# Constant_Current_Sink.net
KiCad netlist of a schematic drawn in Altium Designer
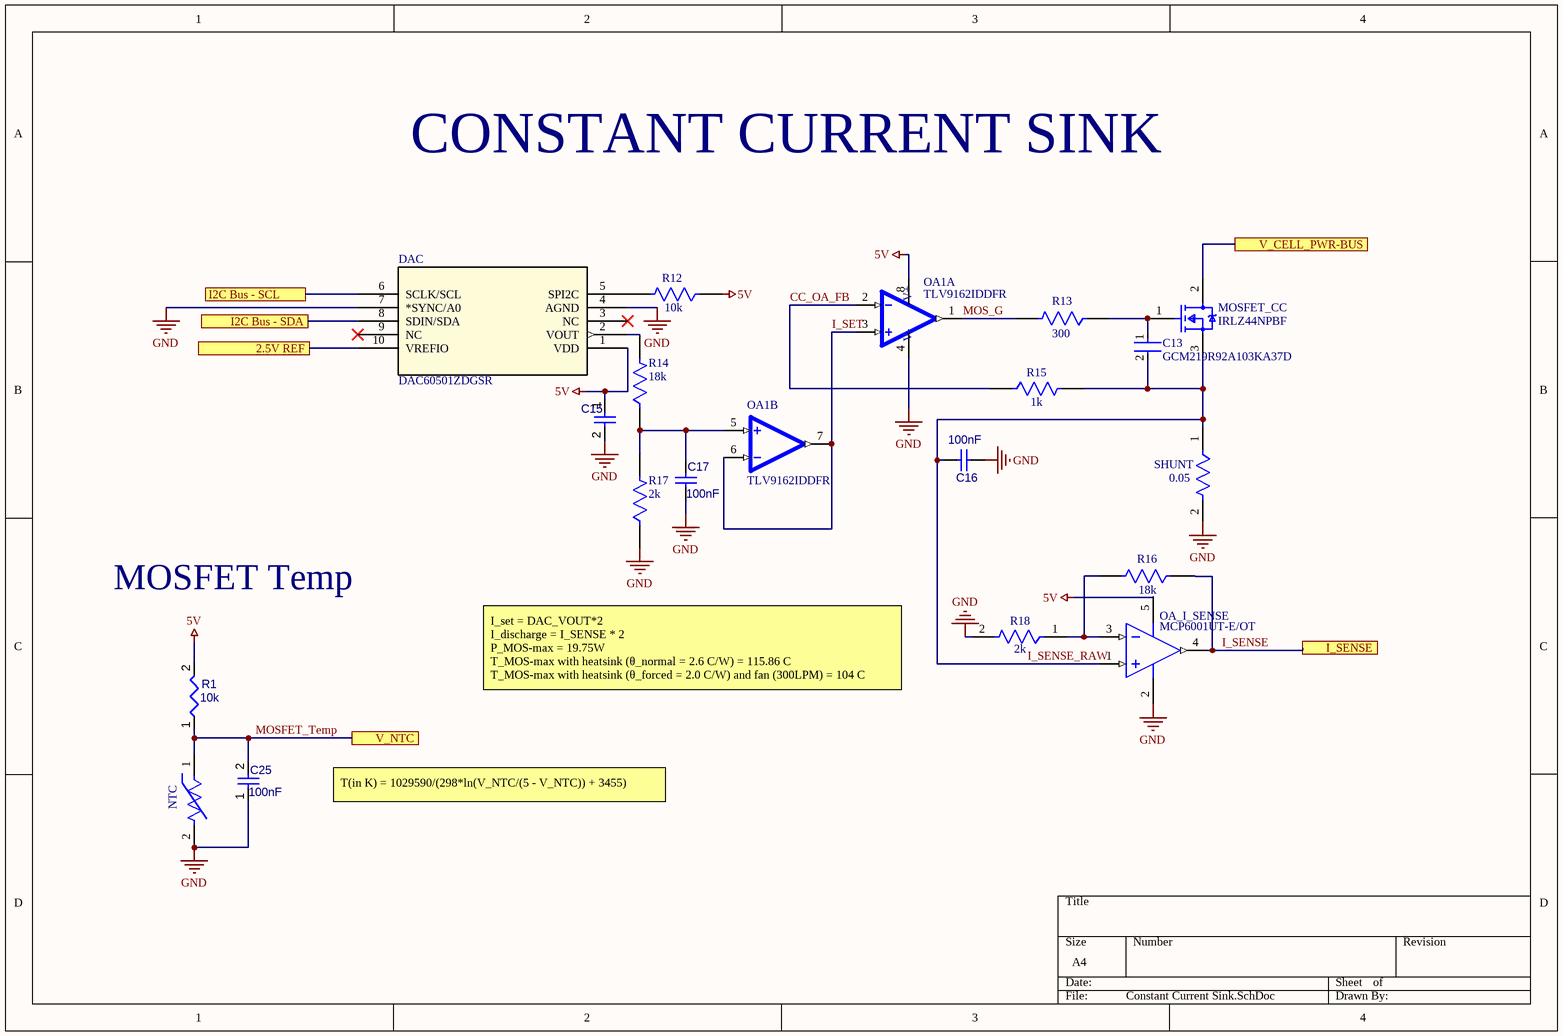
[diagram p0: Constant Current Sink.SchDoc]

(export (version "E")
  (design (tool "Eeschema 10.0.6"))
  (components
    (comp (ref "C13")
      (value "GCM219R92A103KA37D")
      (footprint "FP-GCM219-0_15-IPC_C")
      (description "Ceramic Capacitor for Automotive 10nF  ±10% 100VDC X8R 0805 Paper T/R")
      (libsource (lib "Altium Content Vault") (part "11868f565c42a9108669ba33697ecf6"))
    )
    (comp (ref "C15")
      (value "100nF")
      (footprint "CAPC2013X95X50LL10T25")
      (description "Capacitor 100 nF +/-10% 50 V 0805")
      (fields (field (name "TOLERANCE") "10%"))
      (libsource (lib "gugan Sivakumar") (part "CAP-NP-2"))
    )
    (comp (ref "C16")
      (value "100nF")
      (footprint "CAPC2013X95X50LL10T25")
      (description "Capacitor 100 nF +/-10% 50 V 0805")
      (fields (field (name "TOLERANCE") "10%"))
      (libsource (lib "") (part "CAP-NP-2_1"))
    )
    (comp (ref "C17")
      (value "100nF")
      (footprint "CAPC2013X95X50LL10T25")
      (description "Capacitor 100 nF +/-10% 50 V 0805")
      (fields (field (name "TOLERANCE") "10%"))
      (libsource (lib "") (part "CAP-NP-2_1"))
    )
    (comp (ref "C25")
      (value "100nF")
      (footprint "CAPC2013X95X50LL10T25")
      (description "Capacitor 100 nF +/-10% 50 V 0805")
      (fields (field (name "TOLERANCE") "10%"))
      (libsource (lib "gugan Sivakumar") (part "CAP-NP-2"))
    )
    (comp (ref "DAC")
      (value "DAC60501ZDGSR")
      (footprint "DGS10_TEX")
      (fields (field (name "COPYRIGHT") "Copyright (C) 2025 Ultra Librarian. All rights reserved."))
      (libsource (lib "DAC60501ZDGSR") (part "DAC60501ZDGSR"))
    )
    (comp (ref "MOSFET_CC")
      (value "IRLZ44NPBF")
      (footprint "FP-PG-TO220-3-MFG")
      (description "MOSFET N-CH 55V 47A TO220AB")
      (libsource (lib "Altium Content Vault") (part "b09f7f152735e370c1ea22a33fa83d6"))
    )
    (comp (ref "NTC")
      (value "NXRT15XH103FA1B030")
      (footprint "FP-NXR_151B030-MFG")
      (description "Thermistor NTC 10kΩ ±1% 2-Pin Radial Bulk")
      (fields (field (name "TOLERANCE") "1%"))
      (libsource (lib "Altium Content Vault") (part "3b148a6ebabc5fb4d708a66c052d352"))
    )
    (comp (ref "OA1")
      (value "TLV9162IDDFR")
      (footprint "SOT65P280X110-8N")
      (description "Dual, 16V, 11MHz, rail-to-rail input and output low-offset-voltage low-noise operational amplifier")
      (fields (field (name "MF") "Texas Instruments"))
      (libsource (lib "gugan Sivakumar") (part "TLV9162IDDFR"))
    )
    (comp (ref "OA_I_SENSE")
      (value "MCP6001UT-E/OT")
      (footprint "SOT-23-OT5_L")
      (description "None")
      (libsource (lib "Altium Content Vault") (part "AMP-OPA-MCP6001U-SOT5"))
    )
    (comp (ref "R1")
      (value "10k")
      (footprint "RESC2013X50X35ML15T15")
      (description "Chip Resistor, 10 KOhm, +/- 1%, 125 mW, -55 to 155 degC, 0805 (2012 Metric)")
      (fields (field (name "TOLERANCE") "1%") (field (name "POWER") "125mW"))
      (libsource (lib "gugan Sivakumar") (part "RES-2"))
    )
    (comp (ref "R12")
      (value "10k")
      (footprint "FP-AC0603-IPC_A")
      (description "RES 10kΩ 5.00% 0.2W 0603")
      (libsource (lib "Altium Content Vault") (part "1029c3af85768c4190bb7ad29bc67b5"))
    )
    (comp (ref "R13")
      (value "300")
      (footprint "FP-CR0805-MFG")
      (description "CR0805-FX-3000ELF Thick Film Chip Resistors 0805 300Ω 0.125W 1% 100ppm/°C")
      (fields (field (name "TOLERANCE") "1%"))
      (libsource (lib "Altium Content Vault") (part "1029c3af85768c4190bb7ad29bc67b5"))
    )
    (comp (ref "R14")
      (value "18k")
      (footprint "FP-CRGP0805-IPC_C")
      (description "CRGP0805F18K CRGP0805 18KΩ 0.33W ±100ppm/°C 1% 150V")
      (fields
        (field (name "MANUFACTURER PART NUMBER") "CRGP0805F18K")
        (field (name "OCTOPART") "https://octopart.com/crgp0805f18k-te+connectivity-91018794")
      )
      (libsource (lib "Altium Content Vault") (part "1029c3af85768c4190bb7ad29bc67b5"))
    )
    (comp (ref "R15")
      (value "1k")
      (footprint "FP-RN73R2A-IPC_A")
      (libsource (lib "Altium Content Vault") (part "1029c3af85768c4190bb7ad29bc67b5"))
    )
    (comp (ref "R16")
      (value "18k")
      (footprint "FP-CRGP0805-IPC_C")
      (description "CRGP0805F18K CRGP0805 18KΩ 0.33W ±100ppm/°C 1% 150V")
      (fields
        (field (name "MANUFACTURER PART NUMBER") "CRGP0805F18K")
        (field (name "OCTOPART") "https://octopart.com/crgp0805f18k-te+connectivity-91018794")
      )
      (libsource (lib "Altium Content Vault") (part "1029c3af85768c4190bb7ad29bc67b5"))
    )
    (comp (ref "R17")
      (value "2k")
      (footprint "FP-MCU0805-IPC_A")
      (description "MCU08050D2001BP500 RES 1.05K OHM 0.5% 1/5W 0805")
      (fields (field (name "TOLERANCE") "0.1%"))
      (libsource (lib "Altium Content Vault") (part "1029c3af85768c4190bb7ad29bc67b5"))
    )
    (comp (ref "R18")
      (value "2k")
      (footprint "FP-MCU0805-IPC_A")
      (description "MCU08050D2001BP500 RES 1.05K OHM 0.5% 1/5W 0805")
      (fields (field (name "TOLERANCE") "0.1%"))
      (libsource (lib "") (part "1029c3af85768c4190bb7ad29bc67b5_1"))
    )
    (comp (ref "SHUNT")
      (value "0.05")
      (footprint "FP-CRA2512-IPC_A")
      (description "RES 0.05 OHM 1% 3W 2512")
      (libsource (lib "") (part "1029c3af85768c4190bb7ad29bc67b5_1"))
    )
  )
  (nets
    (net (code "1") (name "/2.5V REF") (class "Default")
      (node (ref "DAC") (pin "10") (pinfunction "VREFIO_10") (pintype "power_in"))
    )
    (net (code "2") (name "/CC_OA_FB") (class "Default")
      (node (ref "OA1") (pin "2") (pinfunction "IN1-_2") (pintype "input"))
      (node (ref "R15") (pin "1") (pinfunction "1_1") (pintype "passive"))
    )
    (net (code "3") (name "/I2C Bus - SCL") (class "Default")
      (node (ref "DAC") (pin "6") (pinfunction "SCLK/SCL_6") (pintype "passive"))
    )
    (net (code "4") (name "/I2C Bus - SDA") (class "Default")
      (node (ref "DAC") (pin "8") (pinfunction "SDIN/SDA_8") (pintype "passive"))
    )
    (net (code "5") (name "/I_SENSE") (class "Default")
      (node (ref "OA_I_SENSE") (pin "4") (pinfunction "VOUT_4") (pintype "output"))
      (node (ref "R16") (pin "1") (pinfunction "1_1") (pintype "passive"))
    )
    (net (code "6") (name "/I_SENSE_RAW") (class "Default")
      (node (ref "C13") (pin "2") (pinfunction "2_2") (pintype "passive"))
      (node (ref "C16") (pin "1") (pinfunction "1_1") (pintype "passive"))
      (node (ref "MOSFET_CC") (pin "3") (pinfunction "S_3") (pintype "passive"))
      (node (ref "OA_I_SENSE") (pin "1") (pinfunction "VIN+_1") (pintype "input"))
      (node (ref "R15") (pin "2") (pinfunction "2_2") (pintype "passive"))
      (node (ref "SHUNT") (pin "1") (pinfunction "1_1") (pintype "passive"))
    )
    (net (code "7") (name "/I_SET") (class "Default")
      (node (ref "OA1") (pin "3") (pinfunction "IN1+_3") (pintype "input"))
      (node (ref "OA1") (pin "6") (pinfunction "IN2-_6") (pintype "input"))
      (node (ref "OA1") (pin "7") (pinfunction "OUT2_7") (pintype "output"))
    )
    (net (code "8") (name "/MOSFET_Temp") (class "Default")
      (node (ref "C25") (pin "2") (pinfunction "2_2") (pintype "passive"))
      (node (ref "NTC") (pin "1") (pinfunction "1_1") (pintype "passive"))
      (node (ref "R1") (pin "1") (pinfunction "1_1") (pintype "passive"))
    )
    (net (code "9") (name "/MOS_G") (class "Default")
      (node (ref "OA1") (pin "1") (pinfunction "OUT1_1") (pintype "output"))
      (node (ref "R13") (pin "2") (pinfunction "2_2") (pintype "passive"))
    )
    (net (code "10") (name "/V_CELL_PWR-BUS") (class "Default")
      (node (ref "MOSFET_CC") (pin "2") (pinfunction "D_2") (pintype "passive"))
    )
    (net (code "11") (name "5V") (class "Default")
      (node (ref "C15") (pin "1") (pinfunction "1_1") (pintype "passive"))
      (node (ref "DAC") (pin "1") (pinfunction "VDD_1") (pintype "power_in"))
      (node (ref "OA1") (pin "8") (pinfunction "V+_8") (pintype "power_in"))
      (node (ref "OA_I_SENSE") (pin "5") (pinfunction "VDD_5") (pintype "power_in"))
      (node (ref "R1") (pin "2") (pinfunction "2_2") (pintype "passive"))
      (node (ref "R12") (pin "1") (pinfunction "1_1") (pintype "passive"))
    )
    (net (code "12") (name "GND") (class "Default")
      (node (ref "C15") (pin "2") (pinfunction "2_2") (pintype "passive"))
      (node (ref "C16") (pin "2") (pinfunction "2_2") (pintype "passive"))
      (node (ref "C17") (pin "2") (pinfunction "2_2") (pintype "passive"))
      (node (ref "C25") (pin "1") (pinfunction "1_1") (pintype "passive"))
      (node (ref "DAC") (pin "4") (pinfunction "AGND_4") (pintype "power_in"))
      (node (ref "DAC") (pin "7") (pinfunction "*SYNC/A0_7") (pintype "passive"))
      (node (ref "NTC") (pin "2") (pinfunction "2_2") (pintype "passive"))
      (node (ref "OA1") (pin "4") (pinfunction "V-_4") (pintype "power_in"))
      (node (ref "OA_I_SENSE") (pin "2") (pinfunction "VSS_2") (pintype "power_in"))
      (node (ref "R17") (pin "1") (pinfunction "1_1") (pintype "passive"))
      (node (ref "R18") (pin "2") (pinfunction "2_2") (pintype "passive"))
      (node (ref "SHUNT") (pin "2") (pinfunction "2_2") (pintype "passive"))
    )
    (net (code "13") (name "Net-(DAC-SPI2C)") (class "Default")
      (node (ref "DAC") (pin "5") (pinfunction "SPI2C_5") (pintype "passive"))
      (node (ref "R12") (pin "2") (pinfunction "2_2") (pintype "passive"))
    )
    (net (code "14") (name "Net-(DAC-VOUT)") (class "Default")
      (node (ref "DAC") (pin "2") (pinfunction "VOUT_2") (pintype "output"))
      (node (ref "R14") (pin "2") (pinfunction "2_2") (pintype "passive"))
    )
    (net (code "15") (name "Net-(MOSFET_CC-G)") (class "Default")
      (node (ref "C13") (pin "1") (pinfunction "1_1") (pintype "passive"))
      (node (ref "MOSFET_CC") (pin "1") (pinfunction "G_1") (pintype "passive"))
      (node (ref "R13") (pin "1") (pinfunction "1_1") (pintype "passive"))
    )
    (net (code "16") (name "Net-(OA1B-IN2+)") (class "Default")
      (node (ref "C17") (pin "1") (pinfunction "1_1") (pintype "passive"))
      (node (ref "OA1") (pin "5") (pinfunction "IN2+_5") (pintype "input"))
      (node (ref "R14") (pin "1") (pinfunction "1_1") (pintype "passive"))
      (node (ref "R17") (pin "2") (pinfunction "2_2") (pintype "passive"))
    )
    (net (code "17") (name "Net-(OA_I_SENSE-VIN-)") (class "Default")
      (node (ref "OA_I_SENSE") (pin "3") (pinfunction "VIN-_3") (pintype "input"))
      (node (ref "R16") (pin "2") (pinfunction "2_2") (pintype "passive"))
      (node (ref "R18") (pin "1") (pinfunction "1_1") (pintype "passive"))
    )
    (net (code "18") (name "unconnected-(DAC-NC-Pad3)") (class "Default")
      (node (ref "DAC") (pin "3") (pinfunction "NC_3") (pintype "passive+no_connect"))
    )
    (net (code "19") (name "unconnected-(DAC-NC-Pad9)") (class "Default")
      (node (ref "DAC") (pin "9") (pinfunction "NC_9") (pintype "passive+no_connect"))
    )
  )
)
